# working.net
KiCad netlist of a schematic drawn in EAGLE
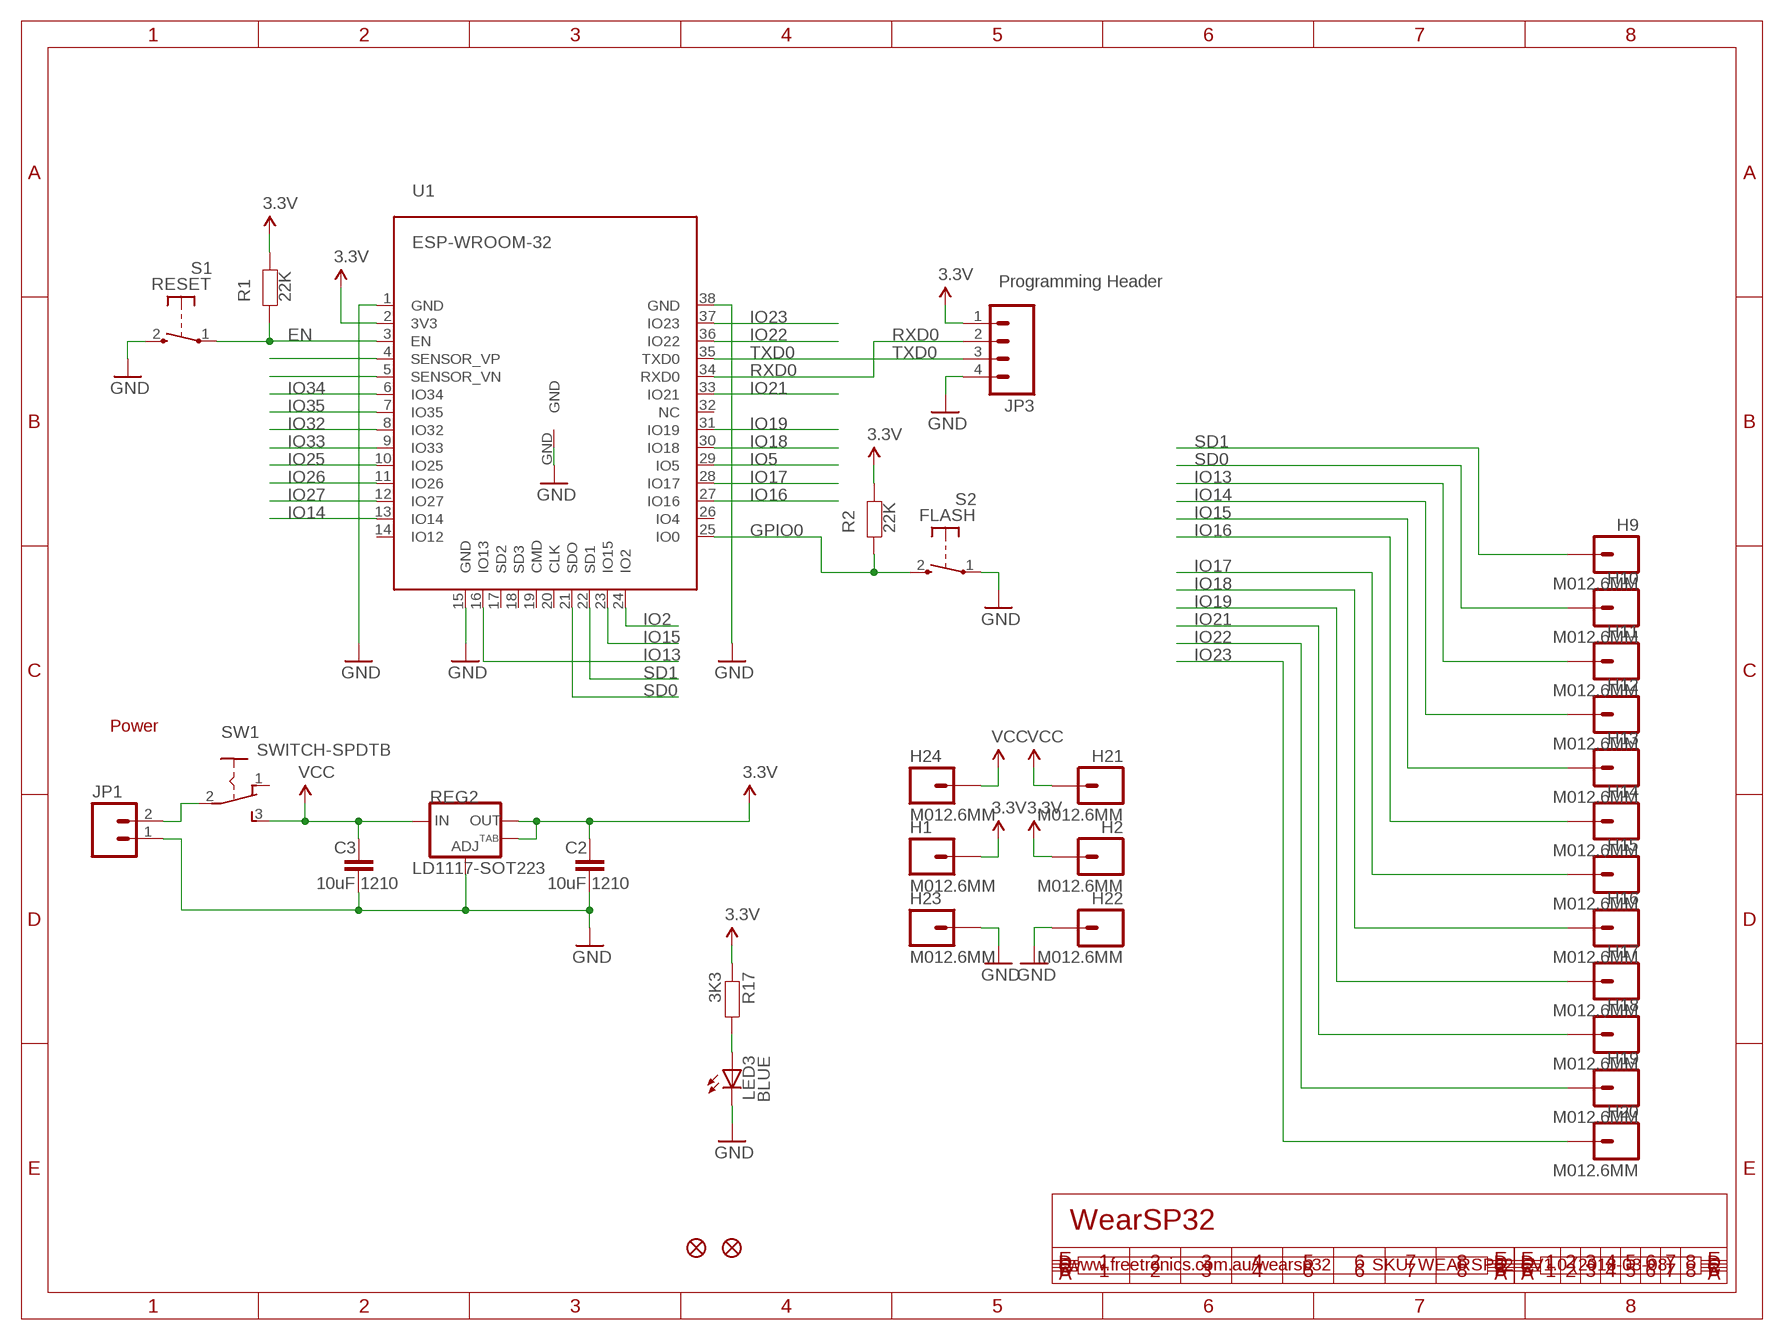
[diagram p0: schematic, sheet 1]

(export (version "E")
  (design (tool "Eeschema 10.0.6"))
  (components
    (comp (ref "C2")
      (value "10uF 1210")
      (footprint "eagle-import:C1210")
      (libsource (lib "eagle-import") (part "C-EUC1210"))
    )
    (comp (ref "C3")
      (value "10uF 1210")
      (footprint "eagle-import:C1210")
      (libsource (lib "eagle-import") (part "C-EUC1210"))
    )
    (comp (ref "H1")
      (value "M012.6MM")
      (footprint "eagle-import:1X01_2_6MM")
      (libsource (lib "eagle-import") (part "M012.6MM"))
    )
    (comp (ref "H2")
      (value "M012.6MM")
      (footprint "eagle-import:1X01_2_6MM")
      (libsource (lib "eagle-import") (part "M012.6MM"))
    )
    (comp (ref "H9")
      (value "M012.6MM")
      (footprint "eagle-import:1X01_2_6MM")
      (libsource (lib "eagle-import") (part "M012.6MM"))
    )
    (comp (ref "H10")
      (value "M012.6MM")
      (footprint "eagle-import:1X01_2_6MM")
      (libsource (lib "eagle-import") (part "M012.6MM"))
    )
    (comp (ref "H11")
      (value "M012.6MM")
      (footprint "eagle-import:1X01_2_6MM")
      (libsource (lib "eagle-import") (part "M012.6MM"))
    )
    (comp (ref "H12")
      (value "M012.6MM")
      (footprint "eagle-import:1X01_2_6MM")
      (libsource (lib "eagle-import") (part "M012.6MM"))
    )
    (comp (ref "H13")
      (value "M012.6MM")
      (footprint "eagle-import:1X01_2_6MM")
      (libsource (lib "eagle-import") (part "M012.6MM"))
    )
    (comp (ref "H14")
      (value "M012.6MM")
      (footprint "eagle-import:1X01_2_6MM")
      (libsource (lib "eagle-import") (part "M012.6MM"))
    )
    (comp (ref "H15")
      (value "M012.6MM")
      (footprint "eagle-import:1X01_2_6MM")
      (libsource (lib "eagle-import") (part "M012.6MM"))
    )
    (comp (ref "H16")
      (value "M012.6MM")
      (footprint "eagle-import:1X01_2_6MM")
      (libsource (lib "eagle-import") (part "M012.6MM"))
    )
    (comp (ref "H17")
      (value "M012.6MM")
      (footprint "eagle-import:1X01_2_6MM")
      (libsource (lib "eagle-import") (part "M012.6MM"))
    )
    (comp (ref "H18")
      (value "M012.6MM")
      (footprint "eagle-import:1X01_2_6MM")
      (libsource (lib "eagle-import") (part "M012.6MM"))
    )
    (comp (ref "H19")
      (value "M012.6MM")
      (footprint "eagle-import:1X01_2_6MM")
      (libsource (lib "eagle-import") (part "M012.6MM"))
    )
    (comp (ref "H20")
      (value "M012.6MM")
      (footprint "eagle-import:1X01_2_6MM")
      (libsource (lib "eagle-import") (part "M012.6MM"))
    )
    (comp (ref "H21")
      (value "M012.6MM")
      (footprint "eagle-import:1X01_2_6MM")
      (libsource (lib "eagle-import") (part "M012.6MM"))
    )
    (comp (ref "H22")
      (value "M012.6MM")
      (footprint "eagle-import:1X01_2_6MM")
      (libsource (lib "eagle-import") (part "M012.6MM"))
    )
    (comp (ref "H23")
      (value "M012.6MM")
      (footprint "eagle-import:1X01_2_6MM")
      (libsource (lib "eagle-import") (part "M012.6MM"))
    )
    (comp (ref "H24")
      (value "M012.6MM")
      (footprint "eagle-import:1X01_2_6MM")
      (libsource (lib "eagle-import") (part "M012.6MM"))
    )
    (comp (ref "JP1")
      (value "M02JST-PTH-2")
      (footprint "eagle-import:JST-2-PTH")
      (libsource (lib "eagle-import") (part "M02JST-PTH-2"))
    )
    (comp (ref "JP3")
      (value "M04PTH")
      (footprint "eagle-import:1X04")
      (libsource (lib "eagle-import") (part "M04PTH"))
    )
    (comp (ref "LED3")
      (value "BLUE")
      (footprint "eagle-import:LED-0603")
      (libsource (lib "eagle-import") (part "LED0603"))
    )
    (comp (ref "R1")
      (value "22K")
      (footprint "eagle-import:0603@2")
      (libsource (lib "eagle-import") (part "RESISTOR0603"))
    )
    (comp (ref "R2")
      (value "22K")
      (footprint "eagle-import:0603@2")
      (libsource (lib "eagle-import") (part "RESISTOR0603"))
    )
    (comp (ref "R17")
      (value "3K3")
      (footprint "eagle-import:0603")
      (libsource (lib "eagle-import") (part "freetronics-jon_RESISTOR0603"))
    )
    (comp (ref "REG2")
      (value "LD1117-SOT223")
      (footprint "eagle-import:SOT223")
      (libsource (lib "eagle-import") (part "V_REG_LM1117SOT223"))
    )
    (comp (ref "S1")
      (value "RESET")
      (footprint "eagle-import:TACTILE_SWITCH_SMD_2PIN_TINY")
      (libsource (lib "eagle-import") (part "TAC_SWITCH_2PIN"))
    )
    (comp (ref "S2")
      (value "FLASH")
      (footprint "eagle-import:TACTILE_SWITCH_SMD_2PIN_TINY")
      (libsource (lib "eagle-import") (part "TAC_SWITCH_2PIN"))
    )
    (comp (ref "SW1")
      (value "SWITCH-SPDTB")
      (footprint "eagle-import:SPDT-2.5MM")
      (libsource (lib "eagle-import") (part "SWITCH-SPDTB"))
    )
    (comp (ref "U$4")
      (value "FIDUCIAL1X2.5")
      (footprint "eagle-import:FIDUCIAL-1X2.5")
      (libsource (lib "eagle-import") (part "FIDUCIAL1X2.5"))
    )
    (comp (ref "U$5")
      (value "FIDUCIAL1X2.5")
      (footprint "eagle-import:FIDUCIAL-1X2.5")
      (libsource (lib "eagle-import") (part "FIDUCIAL1X2.5"))
    )
    (comp (ref "U1")
      (value "ESP-WROOM-32")
      (footprint "eagle-import:ESP-WROOM-32")
      (libsource (lib "eagle-import") (part "ESP-WROOM-32"))
    )
  )
  (nets
    (net (code "1") (name "/EN") (class "Default")
      (node (ref "R1") (pin "2") (pinfunction "2_2") (pintype "passive"))
      (node (ref "S1") (pin "1") (pinfunction "P_1") (pintype "passive"))
      (node (ref "U1") (pin "3") (pinfunction "EN_3") (pintype "bidirectional"))
    )
    (net (code "2") (name "/GPIO0") (class "Default")
      (node (ref "R2") (pin "2") (pinfunction "2_2") (pintype "passive"))
      (node (ref "S2") (pin "2") (pinfunction "S_2") (pintype "passive"))
      (node (ref "U1") (pin "25") (pinfunction "IO0_25") (pintype "bidirectional"))
    )
    (net (code "3") (name "/IO2") (class "Default")
      (node (ref "U1") (pin "24") (pinfunction "IO2_24") (pintype "bidirectional"))
    )
    (net (code "4") (name "/IO5") (class "Default")
      (node (ref "U1") (pin "29") (pinfunction "IO5_29") (pintype "bidirectional"))
    )
    (net (code "5") (name "/IO13") (class "Default")
      (node (ref "H11") (pin "1") (pinfunction "1_1") (pintype "passive"))
      (node (ref "U1") (pin "16") (pinfunction "IO13_16") (pintype "bidirectional"))
    )
    (net (code "6") (name "/IO14") (class "Default")
      (node (ref "H12") (pin "1") (pinfunction "1_1") (pintype "passive"))
      (node (ref "U1") (pin "13") (pinfunction "IO14_13") (pintype "bidirectional"))
    )
    (net (code "7") (name "/IO15") (class "Default")
      (node (ref "H13") (pin "1") (pinfunction "1_1") (pintype "passive"))
      (node (ref "U1") (pin "23") (pinfunction "IO15_23") (pintype "bidirectional"))
    )
    (net (code "8") (name "/IO16") (class "Default")
      (node (ref "H14") (pin "1") (pinfunction "1_1") (pintype "passive"))
      (node (ref "U1") (pin "27") (pinfunction "IO16_27") (pintype "bidirectional"))
    )
    (net (code "9") (name "/IO17") (class "Default")
      (node (ref "H15") (pin "1") (pinfunction "1_1") (pintype "passive"))
      (node (ref "U1") (pin "28") (pinfunction "IO17_28") (pintype "bidirectional"))
    )
    (net (code "10") (name "/IO18") (class "Default")
      (node (ref "H16") (pin "1") (pinfunction "1_1") (pintype "passive"))
      (node (ref "U1") (pin "30") (pinfunction "IO18_30") (pintype "bidirectional"))
    )
    (net (code "11") (name "/IO19") (class "Default")
      (node (ref "H17") (pin "1") (pinfunction "1_1") (pintype "passive"))
      (node (ref "U1") (pin "31") (pinfunction "IO19_31") (pintype "bidirectional"))
    )
    (net (code "12") (name "/IO21") (class "Default")
      (node (ref "H18") (pin "1") (pinfunction "1_1") (pintype "passive"))
      (node (ref "U1") (pin "33") (pinfunction "IO21_33") (pintype "bidirectional"))
    )
    (net (code "13") (name "/IO22") (class "Default")
      (node (ref "H19") (pin "1") (pinfunction "1_1") (pintype "passive"))
      (node (ref "U1") (pin "36") (pinfunction "IO22_36") (pintype "bidirectional"))
    )
    (net (code "14") (name "/IO23") (class "Default")
      (node (ref "H20") (pin "1") (pinfunction "1_1") (pintype "passive"))
      (node (ref "U1") (pin "37") (pinfunction "IO23_37") (pintype "bidirectional"))
    )
    (net (code "15") (name "/IO25") (class "Default")
      (node (ref "U1") (pin "10") (pinfunction "IO25_10") (pintype "bidirectional"))
    )
    (net (code "16") (name "/IO26") (class "Default")
      (node (ref "U1") (pin "11") (pinfunction "IO26_11") (pintype "bidirectional"))
    )
    (net (code "17") (name "/IO27") (class "Default")
      (node (ref "U1") (pin "12") (pinfunction "IO27_12") (pintype "bidirectional"))
    )
    (net (code "18") (name "/IO32") (class "Default")
      (node (ref "U1") (pin "8") (pinfunction "IO32_8") (pintype "bidirectional"))
    )
    (net (code "19") (name "/IO33") (class "Default")
      (node (ref "U1") (pin "9") (pinfunction "IO33_9") (pintype "bidirectional"))
    )
    (net (code "20") (name "/IO34") (class "Default")
      (node (ref "U1") (pin "6") (pinfunction "IO34_6") (pintype "bidirectional"))
    )
    (net (code "21") (name "/IO35") (class "Default")
      (node (ref "U1") (pin "7") (pinfunction "IO35_7") (pintype "bidirectional"))
    )
    (net (code "22") (name "/RXD0") (class "Default")
      (node (ref "JP3") (pin "2") (pinfunction "2_2") (pintype "passive"))
      (node (ref "U1") (pin "34") (pinfunction "RXD0_34") (pintype "bidirectional"))
    )
    (net (code "23") (name "/SD0") (class "Default")
      (node (ref "H10") (pin "1") (pinfunction "1_1") (pintype "passive"))
      (node (ref "U1") (pin "21") (pinfunction "SDO_21") (pintype "bidirectional"))
    )
    (net (code "24") (name "/SD1") (class "Default")
      (node (ref "H9") (pin "1") (pinfunction "1_1") (pintype "passive"))
      (node (ref "U1") (pin "22") (pinfunction "SD1_22") (pintype "bidirectional"))
    )
    (net (code "25") (name "/TXD0") (class "Default")
      (node (ref "JP3") (pin "3") (pinfunction "3_3") (pintype "passive"))
      (node (ref "U1") (pin "35") (pinfunction "TXD0_35") (pintype "bidirectional"))
    )
    (net (code "26") (name "3.3V") (class "Default")
      (node (ref "C2") (pin "1") (pinfunction "1_1") (pintype "passive"))
      (node (ref "H1") (pin "1") (pinfunction "1_1") (pintype "passive"))
      (node (ref "H2") (pin "1") (pinfunction "1_1") (pintype "passive"))
      (node (ref "JP3") (pin "1") (pinfunction "1_1") (pintype "passive"))
      (node (ref "R1") (pin "1") (pinfunction "1_1") (pintype "passive"))
      (node (ref "R17") (pin "1") (pinfunction "1_1") (pintype "passive"))
      (node (ref "R2") (pin "1") (pinfunction "1_1") (pintype "passive"))
      (node (ref "REG2") (pin "2") (pinfunction "OUT_2") (pintype "output"))
      (node (ref "REG2") (pin "4") (pinfunction "OUT_4") (pintype "output"))
      (node (ref "U1") (pin "2") (pinfunction "3V3_2") (pintype "bidirectional"))
    )
    (net (code "27") (name "GND") (class "Default")
      (node (ref "C2") (pin "2") (pinfunction "2_2") (pintype "passive"))
      (node (ref "C3") (pin "2") (pinfunction "2_2") (pintype "passive"))
      (node (ref "H22") (pin "1") (pinfunction "1_1") (pintype "passive"))
      (node (ref "H23") (pin "1") (pinfunction "1_1") (pintype "passive"))
      (node (ref "JP1") (pin "1") (pinfunction "1_1") (pintype "passive"))
      (node (ref "JP3") (pin "4") (pinfunction "4_4") (pintype "passive"))
      (node (ref "LED3") (pin "C") (pinfunction "C_C") (pintype "passive"))
      (node (ref "REG2") (pin "1") (pinfunction "ADJ_1") (pintype "input"))
      (node (ref "S1") (pin "2") (pinfunction "S_2") (pintype "passive"))
      (node (ref "S2") (pin "1") (pinfunction "P_1") (pintype "passive"))
      (node (ref "U1") (pin "1") (pinfunction "GND_1") (pintype "bidirectional"))
      (node (ref "U1") (pin "15") (pinfunction "GND_15") (pintype "bidirectional"))
      (node (ref "U1") (pin "38") (pinfunction "GND_38") (pintype "bidirectional"))
      (node (ref "U1") (pin "GND") (pinfunction "GND_GND") (pintype "bidirectional"))
    )
    (net (code "28") (name "Net-(JP1-Pad2)") (class "Default")
      (node (ref "JP1") (pin "2") (pinfunction "2_2") (pintype "passive"))
      (node (ref "SW1") (pin "2") (pinfunction "2_2") (pintype "passive"))
    )
    (net (code "29") (name "Net-(LED3-PadA)") (class "Default")
      (node (ref "LED3") (pin "A") (pinfunction "A_A") (pintype "passive"))
      (node (ref "R17") (pin "2") (pinfunction "2_2") (pintype "passive"))
    )
    (net (code "30") (name "VCC") (class "Default")
      (node (ref "C3") (pin "1") (pinfunction "1_1") (pintype "passive"))
      (node (ref "H21") (pin "1") (pinfunction "1_1") (pintype "passive"))
      (node (ref "H24") (pin "1") (pinfunction "1_1") (pintype "passive"))
      (node (ref "REG2") (pin "3") (pinfunction "IN_3") (pintype "input"))
      (node (ref "SW1") (pin "3") (pinfunction "3_3") (pintype "passive"))
    )
    (net (code "31") (name "unconnected-(SW1-Pad1)") (class "Default")
      (node (ref "SW1") (pin "1") (pinfunction "1_1") (pintype "passive"))
    )
    (net (code "32") (name "unconnected-(U1-CLK-Pad20)") (class "Default")
      (node (ref "U1") (pin "20") (pinfunction "CLK_20") (pintype "bidirectional"))
    )
    (net (code "33") (name "unconnected-(U1-CMD-Pad19)") (class "Default")
      (node (ref "U1") (pin "19") (pinfunction "CMD_19") (pintype "bidirectional"))
    )
    (net (code "34") (name "unconnected-(U1-IO4-Pad26)") (class "Default")
      (node (ref "U1") (pin "26") (pinfunction "IO4_26") (pintype "bidirectional"))
    )
    (net (code "35") (name "unconnected-(U1-IO12-Pad14)") (class "Default")
      (node (ref "U1") (pin "14") (pinfunction "IO12_14") (pintype "bidirectional"))
    )
    (net (code "36") (name "unconnected-(U1-NC-Pad32)") (class "Default")
      (node (ref "U1") (pin "32") (pinfunction "NC_32") (pintype "bidirectional"))
    )
    (net (code "37") (name "unconnected-(U1-SD2-Pad17)") (class "Default")
      (node (ref "U1") (pin "17") (pinfunction "SD2_17") (pintype "bidirectional"))
    )
    (net (code "38") (name "unconnected-(U1-SD3-Pad18)") (class "Default")
      (node (ref "U1") (pin "18") (pinfunction "SD3_18") (pintype "bidirectional"))
    )
    (net (code "39") (name "unconnected-(U1-SENSOR_VN-Pad5)") (class "Default")
      (node (ref "U1") (pin "5") (pinfunction "SENSOR_VN_5") (pintype "bidirectional"))
    )
    (net (code "40") (name "unconnected-(U1-SENSOR_VP-Pad4)") (class "Default")
      (node (ref "U1") (pin "4") (pinfunction "SENSOR_VP_4") (pintype "bidirectional"))
    )
  )
)
